# 17_MIPI_CSI_RX.net
KiCad netlist of a schematic drawn in Altium Designer
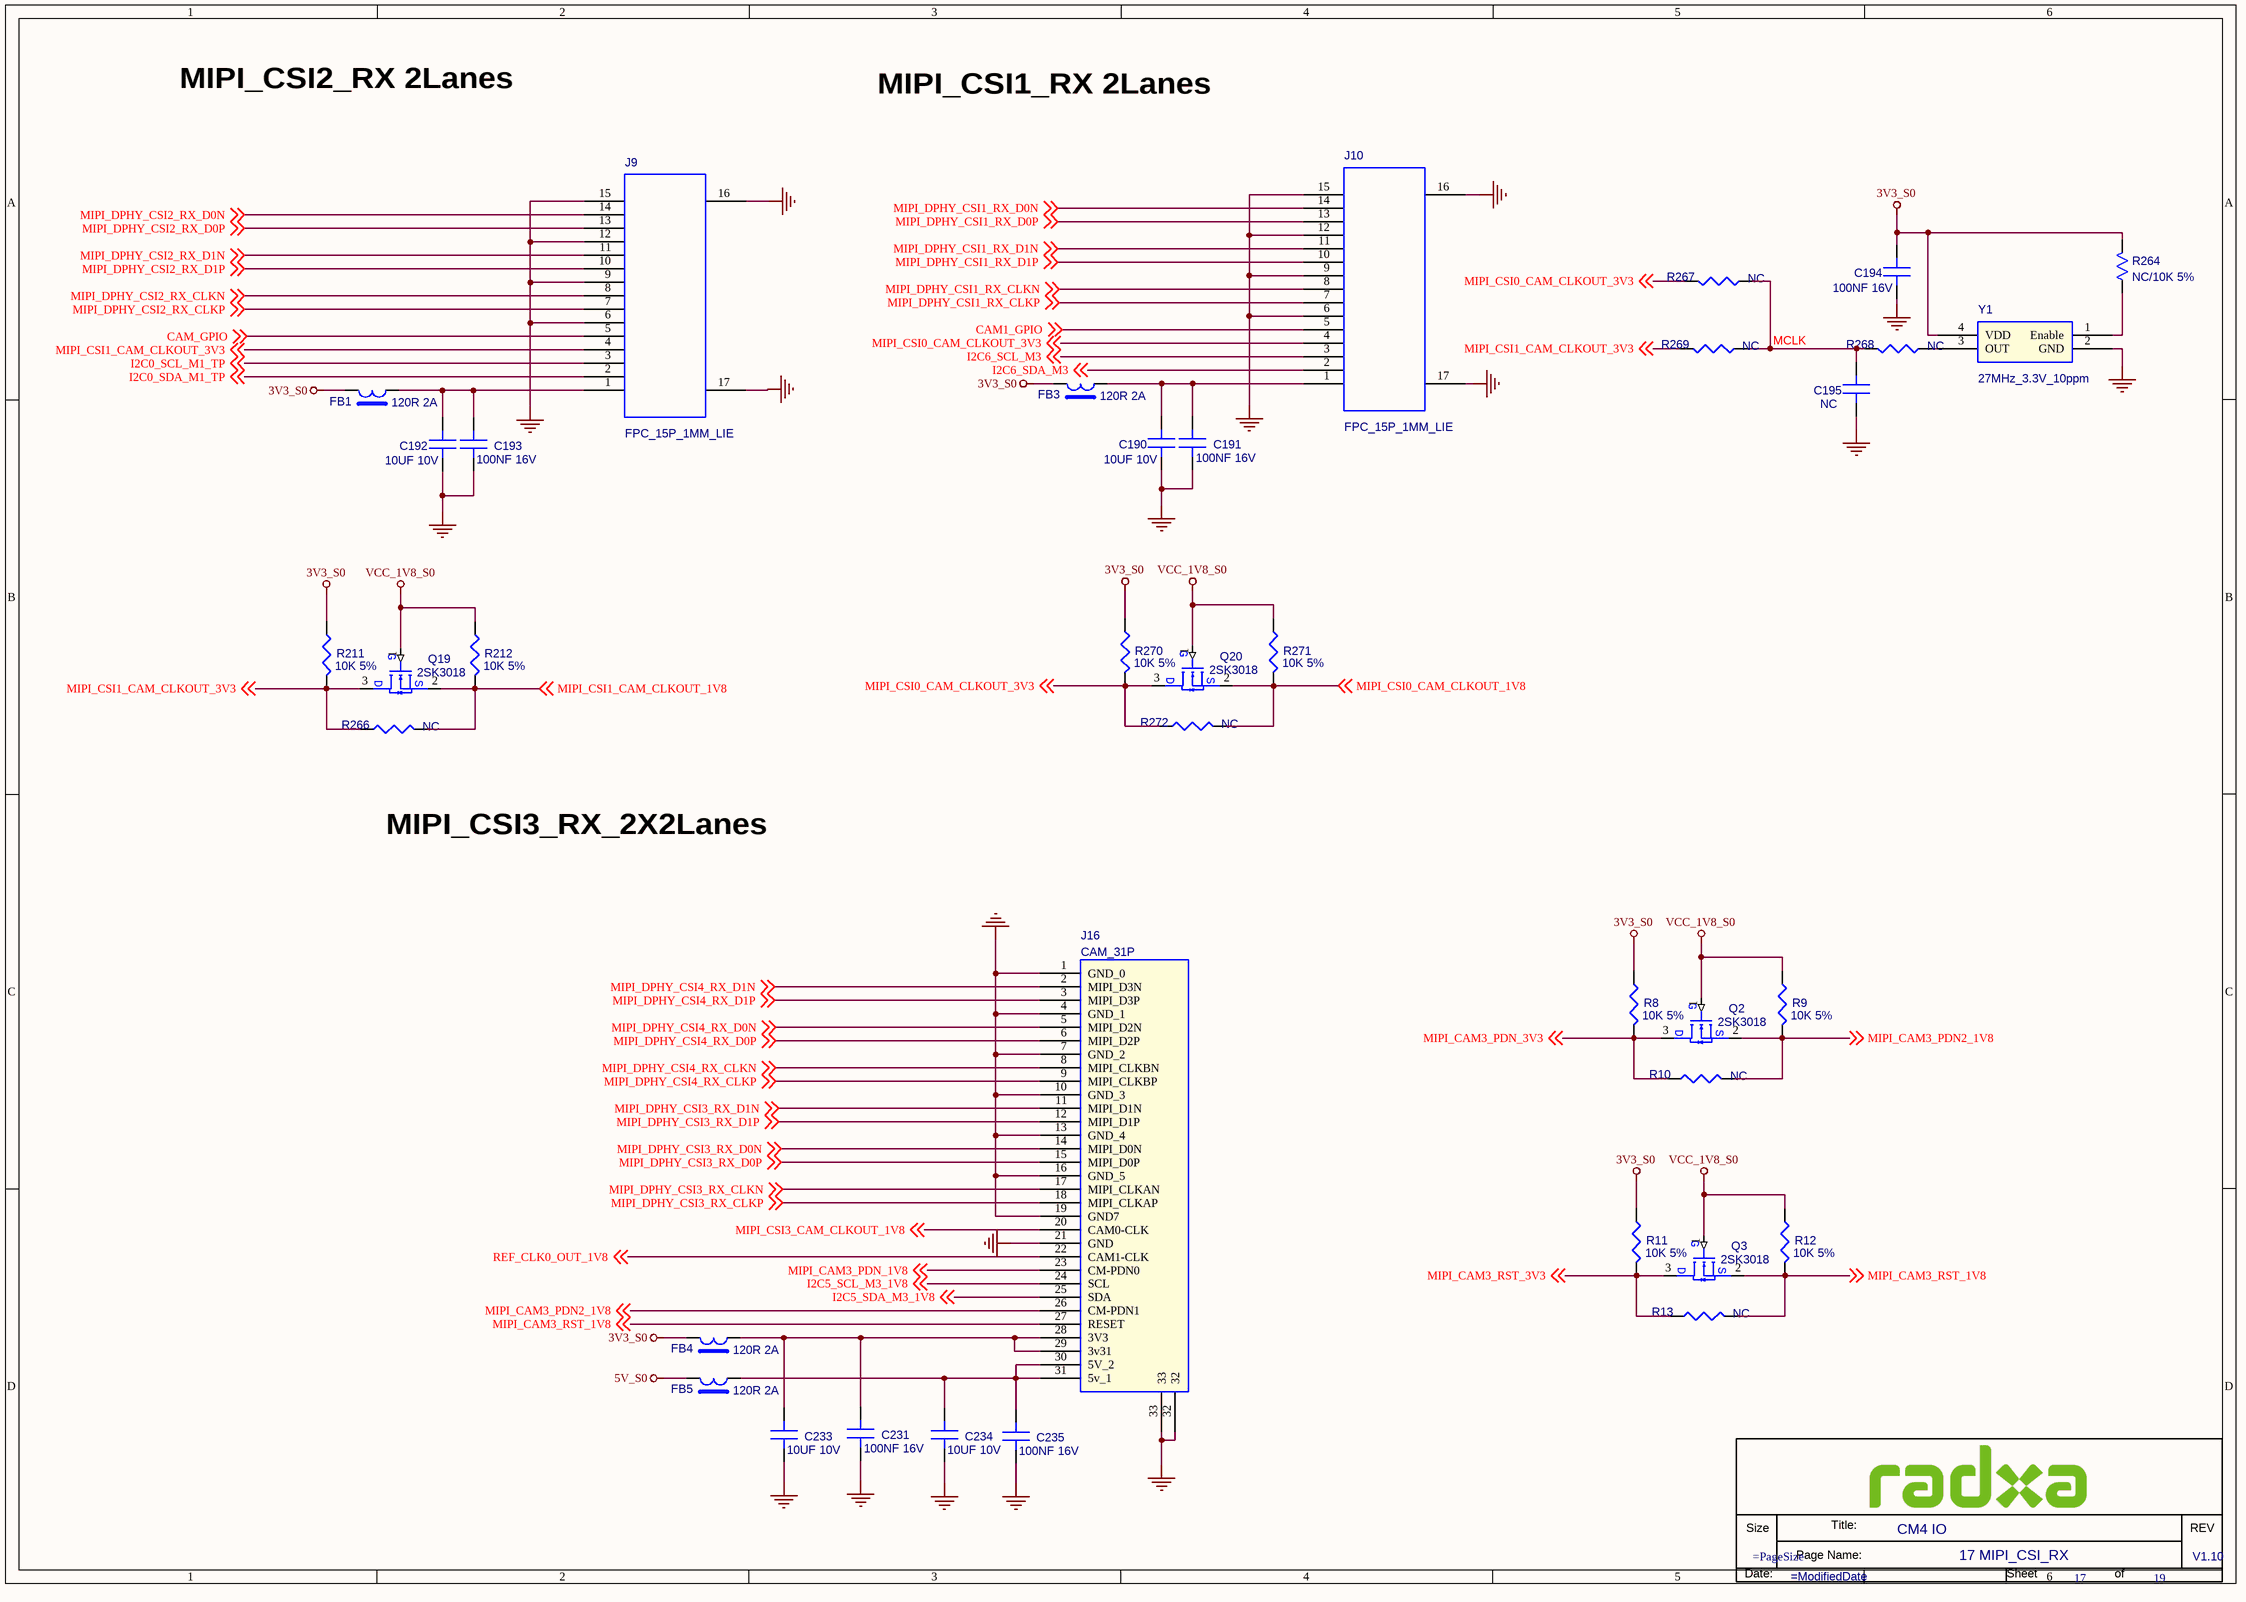
[diagram p0: 17 MIPI_CSI_RX.SchDoc]

(export (version "E")
  (design (tool "Eeschema 10.0.6"))
  (components
    (comp (ref "C190")
      (value "10UF 10V")
      (footprint "C0402")
      (description "SMD  0402  10UF  10V  X5R  ±20%  ROHS")
      (fields (field (name "PART NUMBER") "A1C01.00025"))
      (libsource (lib "*") (part "C"))
    )
    (comp (ref "C191")
      (value "100NF 16V")
      (footprint "C0201")
      (description "SMD  0201  100NF  16V  X5R  ±20%  ROHS")
      (fields (field (name "PART NUMBER") "A1C01.00099"))
      (libsource (lib "*") (part "C"))
    )
    (comp (ref "C192")
      (value "10UF 10V")
      (footprint "C0402")
      (description "SMD  0402  10UF  10V  X5R  ±20%  ROHS")
      (fields (field (name "PART NUMBER") "A1C01.00025"))
      (libsource (lib "*") (part "C"))
    )
    (comp (ref "C193")
      (value "100NF 16V")
      (footprint "C0201")
      (description "SMD  0201  100NF  16V  X5R  ±20%  ROHS")
      (fields (field (name "PART NUMBER") "A1C01.00099"))
      (libsource (lib "*") (part "C"))
    )
    (comp (ref "C194")
      (value "100NF 16V")
      (footprint "C0201")
      (description "SMD  0201  100NF  16V  X5R  ±20%  ROHS")
      (fields (field (name "PART NUMBER") "A1C01.00099") (field (name "APPROVED") "已承认"))
      (libsource (lib "*") (part "C_Dup1"))
    )
    (comp (ref "C195")
      (value "NC")
      (footprint "C0201")
      (description "SMD  0201  10PF  50V  NPO  ±5%  ROHS")
      (fields (field (name "PART NUMBER") "A1C01.00141") (field (name "APPROVED") "已承认"))
      (libsource (lib "*") (part "C_Dup1"))
    )
    (comp (ref "C231")
      (value "100NF 16V")
      (footprint "C0201")
      (description "SMD  0201  100NF  16V  X5R  ±20%  ROHS")
      (fields (field (name "PART NUMBER") "A1C01.00099"))
      (libsource (lib "*") (part "C"))
    )
    (comp (ref "C233")
      (value "10UF 10V")
      (footprint "C0402")
      (description "SMD  0402  10UF  10V  X5R  ±20%  ROHS")
      (fields (field (name "PART NUMBER") "A1C01.00025"))
      (libsource (lib "*") (part "C"))
    )
    (comp (ref "C234")
      (value "10UF 10V")
      (footprint "C0402")
      (description "SMD  0402  10UF  10V  X5R  ±20%  ROHS")
      (fields (field (name "PART NUMBER") "A1C01.00025"))
      (libsource (lib "*") (part "C"))
    )
    (comp (ref "C235")
      (value "100NF 16V")
      (footprint "C0201")
      (description "SMD  0201  100NF  16V  X5R  ±20%  ROHS")
      (fields (field (name "PART NUMBER") "A1C01.00099"))
      (libsource (lib "*") (part "C"))
    )
    (comp (ref "FB1")
      (value "120R 2A")
      (footprint "FB0402")
      (description "SMD  0402  FB120R  2A  ±25%  ROHS")
      (fields (field (name "PART NUMBER") "A1L09.00004"))
      (libsource (lib "*") (part "BEAD"))
    )
    (comp (ref "FB3")
      (value "120R 2A")
      (footprint "FB0402")
      (description "SMD  0402  FB120R  2A  ±25%  ROHS")
      (fields (field (name "PART NUMBER") "A1L09.00004"))
      (libsource (lib "*") (part "BEAD"))
    )
    (comp (ref "FB4")
      (value "120R 2A")
      (footprint "FB0402")
      (description "SMD  0402  FB120R  2A  ±25%  ROHS")
      (fields (field (name "PART NUMBER") "A1L09.00004"))
      (libsource (lib "*") (part "BEAD"))
    )
    (comp (ref "FB5")
      (value "120R 2A")
      (footprint "FB0402")
      (description "SMD  0402  FB120R  2A  ±25%  ROHS")
      (fields (field (name "PART NUMBER") "A1L09.00004"))
      (libsource (lib "*") (part "BEAD"))
    )
    (comp (ref "J9")
      (value "FPC_15P_1MM_LIE")
      (footprint "FPC_15_1D0_LIE")
      (description "SMD  翻盖式下接触  卧式  15PIN  180度  1.0mm脚距  H2.0  FPC-1.0FX-15PWCR-H20  XUNPU(讯普)  ROHS")
      (fields (field (name "PART NUMBER") "A1J06.00025"))
      (libsource (lib "*") (part "FPC_15P_LIE"))
    )
    (comp (ref "J10")
      (value "FPC_15P_1MM_LIE")
      (footprint "FPC_15_1D0_LIE")
      (description "SMD  翻盖式下接触  卧式  15PIN  180度  1.0mm脚距  H2.0  FPC-1.0FX-15PWCR-H20  XUNPU(讯普)  ROHS")
      (fields (field (name "PART NUMBER") "A1J06.00025"))
      (libsource (lib "*") (part "FPC_15P_LIE"))
    )
    (comp (ref "J16")
      (value "CAM_31P")
      (footprint "FPC_31P_0d3_LIE")
      (description "SMD  上下接触  卧式  31PIN  0.3mm脚距  后翻盖H1.0  FH35C-31S-0.3SHW(50)  镀金  广濑  ROHS")
      (fields (field (name "PART NUMBER") "A1J06.00002"))
      (libsource (lib "*") (part "CAM_31P"))
    )
    (comp (ref "Q2")
      (value "2SK3018")
      (footprint "SOT_323")
      (description "SMD  编带  SOT-323  2SK3018  N沟道  长晶  ROHS")
      (fields (field (name "PART NUMBER") "A1D01.00007"))
      (libsource (lib "*") (part "MOSFET_NPN"))
    )
    (comp (ref "Q3")
      (value "2SK3018")
      (footprint "SOT_323")
      (description "SMD  编带  SOT-323  2SK3018  N沟道  长晶  ROHS")
      (fields (field (name "PART NUMBER") "A1D01.00007"))
      (libsource (lib "*") (part "MOSFET_NPN"))
    )
    (comp (ref "Q19")
      (value "2SK3018")
      (footprint "SOT_323")
      (description "SMD  编带  SOT-323  2SK3018  N沟道  长晶  ROHS")
      (fields (field (name "PART NUMBER") "A1D01.00007"))
      (libsource (lib "*") (part "MOSFET_NPN"))
    )
    (comp (ref "Q20")
      (value "2SK3018")
      (footprint "SOT_323")
      (description "SMD  编带  SOT-323  2SK3018  N沟道  长晶  ROHS")
      (fields (field (name "PART NUMBER") "A1D01.00007"))
      (libsource (lib "*") (part "MOSFET_NPN"))
    )
    (comp (ref "R8")
      (value "10K 5%")
      (footprint "R0402")
      (description "SMD  0201  10K  1/20W  ±5%  ROHS")
      (fields (field (name "PART NUMBER") "A1R01.00012"))
      (libsource (lib "*") (part "R"))
    )
    (comp (ref "R9")
      (value "10K 5%")
      (footprint "R0402")
      (description "SMD  0201  10K  1/20W  ±5%  ROHS")
      (fields (field (name "PART NUMBER") "A1R01.00012"))
      (libsource (lib "*") (part "R"))
    )
    (comp (ref "R10")
      (value "NC")
      (footprint "R0402")
      (description "SMD  0201  0R  1/20W  ±5%  ROHS")
      (fields (field (name "PART NUMBER") "A1R01.00027"))
      (libsource (lib "*") (part "R"))
    )
    (comp (ref "R11")
      (value "10K 5%")
      (footprint "R0402")
      (description "SMD  0201  10K  1/20W  ±5%  ROHS")
      (fields (field (name "PART NUMBER") "A1R01.00012"))
      (libsource (lib "*") (part "R"))
    )
    (comp (ref "R12")
      (value "10K 5%")
      (footprint "R0402")
      (description "SMD  0201  10K  1/20W  ±5%  ROHS")
      (fields (field (name "PART NUMBER") "A1R01.00012"))
      (libsource (lib "*") (part "R"))
    )
    (comp (ref "R13")
      (value "NC")
      (footprint "R0402")
      (description "SMD  0201  0R  1/20W  ±5%  ROHS")
      (fields (field (name "PART NUMBER") "A1R01.00027"))
      (libsource (lib "*") (part "R"))
    )
    (comp (ref "R211")
      (value "10K 5%")
      (footprint "R0402")
      (description "SMD  0201  10K  1/20W  ±5%  ROHS")
      (fields (field (name "PART NUMBER") "A1R01.00012"))
      (libsource (lib "*") (part "R"))
    )
    (comp (ref "R212")
      (value "10K 5%")
      (footprint "R0402")
      (description "SMD  0201  10K  1/20W  ±5%  ROHS")
      (fields (field (name "PART NUMBER") "A1R01.00012"))
      (libsource (lib "*") (part "R"))
    )
    (comp (ref "R264")
      (value "NC/10K 5%")
      (footprint "R0201")
      (description "SMD  0201  10K  1/20W  ±5%  ROHS")
      (fields (field (name "PART NUMBER") "A1R01.00012") (field (name "APPROVED") "已承认"))
      (libsource (lib "*") (part "R_Dup1"))
    )
    (comp (ref "R266")
      (value "NC")
      (footprint "R0402")
      (description "SMD  0201  0R  1/20W  ±5%  ROHS")
      (fields (field (name "PART NUMBER") "A1R01.00027"))
      (libsource (lib "*") (part "R"))
    )
    (comp (ref "R267")
      (value "NC")
      (footprint "R0402")
      (description "SMD  0201  0R  1/20W  ±5%  ROHS")
      (fields (field (name "PART NUMBER") "A1R01.00027"))
      (libsource (lib "*") (part "R"))
    )
    (comp (ref "R268")
      (value "NC")
      (footprint "R0402")
      (description "SMD  0201  0R  1/20W  ±5%  ROHS")
      (fields (field (name "PART NUMBER") "A1R01.00027"))
      (libsource (lib "*") (part "R"))
    )
    (comp (ref "R269")
      (value "NC")
      (footprint "R0402")
      (description "SMD  0201  0R  1/20W  ±5%  ROHS")
      (fields (field (name "PART NUMBER") "A1R01.00027"))
      (libsource (lib "*") (part "R"))
    )
    (comp (ref "R270")
      (value "10K 5%")
      (footprint "R0402")
      (description "SMD  0201  10K  1/20W  ±5%  ROHS")
      (fields (field (name "PART NUMBER") "A1R01.00012"))
      (libsource (lib "*") (part "R"))
    )
    (comp (ref "R271")
      (value "10K 5%")
      (footprint "R0402")
      (description "SMD  0201  10K  1/20W  ±5%  ROHS")
      (fields (field (name "PART NUMBER") "A1R01.00012"))
      (libsource (lib "*") (part "R"))
    )
    (comp (ref "R272")
      (value "NC")
      (footprint "R0402")
      (description "SMD  0201  0R  1/20W  ±5%  ROHS")
      (fields (field (name "PART NUMBER") "A1R01.00027"))
      (libsource (lib "*") (part "R"))
    )
    (comp (ref "Y1")
      (value "27MHz_3.3V_10ppm")
      (footprint "Y-4-5_08-TXC-7W5")
      (description "SMD  有源  3225  27MHz  3.3V  ±10ppm  晶灏  3N27.000E33YCG  ROHS")
      (fields (field (name "PART NUMBER") "A1Y01.00074"))
      (libsource (lib "*") (part "OSC_4P_V"))
    )
  )
  (nets
    (net (code "1") (name "/MCLK") (class "Default")
      (node (ref "C195") (pin "1") (pinfunction "1_1") (pintype "passive"))
      (node (ref "R267") (pin "1") (pinfunction "1_1") (pintype "passive"))
      (node (ref "R268") (pin "1") (pinfunction "1_1") (pintype "passive"))
      (node (ref "R269") (pin "1") (pinfunction "1_1") (pintype "passive"))
    )
    (net (code "2") (name "3V3_S0") (class "Default")
      (node (ref "C194") (pin "1") (pinfunction "1_1") (pintype "passive"))
      (node (ref "FB1") (pin "2") (pinfunction "2_2") (pintype "passive"))
      (node (ref "FB3") (pin "2") (pinfunction "2_2") (pintype "passive"))
      (node (ref "FB4") (pin "2") (pinfunction "2_2") (pintype "passive"))
      (node (ref "R11") (pin "2") (pinfunction "2_2") (pintype "passive"))
      (node (ref "R211") (pin "2") (pinfunction "2_2") (pintype "passive"))
      (node (ref "R264") (pin "2") (pinfunction "2_2") (pintype "passive"))
      (node (ref "R270") (pin "2") (pinfunction "2_2") (pintype "passive"))
      (node (ref "R8") (pin "2") (pinfunction "2_2") (pintype "passive"))
      (node (ref "Y1") (pin "4") (pinfunction "VDD_4") (pintype "passive"))
    )
    (net (code "3") (name "5V_S0") (class "Default")
      (node (ref "FB5") (pin "2") (pinfunction "2_2") (pintype "passive"))
    )
    (net (code "4") (name "CAM1_GPIO") (class "Default")
      (node (ref "J10") (pin "5") (pinfunction "5_5") (pintype "passive"))
    )
    (net (code "5") (name "CAM_GPIO") (class "Default")
      (node (ref "J9") (pin "5") (pinfunction "5_5") (pintype "passive"))
    )
    (net (code "6") (name "GND") (class "Default")
      (node (ref "C190") (pin "2") (pinfunction "B_2") (pintype "passive"))
      (node (ref "C191") (pin "2") (pinfunction "B_2") (pintype "passive"))
      (node (ref "C192") (pin "2") (pinfunction "B_2") (pintype "passive"))
      (node (ref "C193") (pin "2") (pinfunction "B_2") (pintype "passive"))
      (node (ref "C194") (pin "2") (pinfunction "2_2") (pintype "passive"))
      (node (ref "C195") (pin "2") (pinfunction "2_2") (pintype "passive"))
      (node (ref "C231") (pin "2") (pinfunction "B_2") (pintype "passive"))
      (node (ref "C233") (pin "2") (pinfunction "B_2") (pintype "passive"))
      (node (ref "C234") (pin "2") (pinfunction "B_2") (pintype "passive"))
      (node (ref "C235") (pin "2") (pinfunction "B_2") (pintype "passive"))
      (node (ref "J10") (pin "12") (pinfunction "12_12") (pintype "passive"))
      (node (ref "J10") (pin "15") (pinfunction "15_15") (pintype "passive"))
      (node (ref "J10") (pin "16") (pinfunction "16_16") (pintype "passive"))
      (node (ref "J10") (pin "17") (pinfunction "17_17") (pintype "passive"))
      (node (ref "J10") (pin "6") (pinfunction "6_6") (pintype "passive"))
      (node (ref "J10") (pin "9") (pinfunction "9_9") (pintype "passive"))
      (node (ref "J16") (pin "1") (pinfunction "GND_0_1") (pintype "passive"))
      (node (ref "J16") (pin "10") (pinfunction "GND_3_10") (pintype "passive"))
      (node (ref "J16") (pin "13") (pinfunction "GND_4_13") (pintype "passive"))
      (node (ref "J16") (pin "16") (pinfunction "GND_5_16") (pintype "passive"))
      (node (ref "J16") (pin "19") (pinfunction "GND7_19") (pintype "passive"))
      (node (ref "J16") (pin "21") (pinfunction "GND_21") (pintype "passive"))
      (node (ref "J16") (pin "32") (pinfunction "32_32") (pintype "passive"))
      (node (ref "J16") (pin "33") (pinfunction "33_33") (pintype "passive"))
      (node (ref "J16") (pin "4") (pinfunction "GND_1_4") (pintype "passive"))
      (node (ref "J16") (pin "7") (pinfunction "GND_2_7") (pintype "passive"))
      (node (ref "J9") (pin "12") (pinfunction "12_12") (pintype "passive"))
      (node (ref "J9") (pin "15") (pinfunction "15_15") (pintype "passive"))
      (node (ref "J9") (pin "16") (pinfunction "16_16") (pintype "passive"))
      (node (ref "J9") (pin "17") (pinfunction "17_17") (pintype "passive"))
      (node (ref "J9") (pin "6") (pinfunction "6_6") (pintype "passive"))
      (node (ref "J9") (pin "9") (pinfunction "9_9") (pintype "passive"))
      (node (ref "Y1") (pin "2") (pinfunction "GND_2") (pintype "passive"))
    )
    (net (code "7") (name "I2C0_SCL_M1_TP") (class "Default")
      (node (ref "J9") (pin "3") (pinfunction "3_3") (pintype "passive"))
    )
    (net (code "8") (name "I2C0_SDA_M1_TP") (class "Default")
      (node (ref "J9") (pin "2") (pinfunction "2_2") (pintype "passive"))
    )
    (net (code "9") (name "I2C5_SCL_M3_1V8") (class "Default")
      (node (ref "J16") (pin "24") (pinfunction "SCL_24") (pintype "passive"))
    )
    (net (code "10") (name "I2C5_SDA_M3_1V8") (class "Default")
      (node (ref "J16") (pin "25") (pinfunction "SDA_25") (pintype "passive"))
    )
    (net (code "11") (name "I2C6_SCL_M3") (class "Default")
      (node (ref "J10") (pin "3") (pinfunction "3_3") (pintype "passive"))
    )
    (net (code "12") (name "I2C6_SDA_M3") (class "Default")
      (node (ref "J10") (pin "2") (pinfunction "2_2") (pintype "passive"))
    )
    (net (code "13") (name "MIPI_CAM3_PDN2_1V8") (class "Default")
      (node (ref "J16") (pin "26") (pinfunction "CM-PDN1_26") (pintype "passive"))
      (node (ref "Q2") (pin "2") (pinfunction "S_2") (pintype "passive"))
      (node (ref "R10") (pin "1") (pinfunction "1_1") (pintype "passive"))
      (node (ref "R9") (pin "1") (pinfunction "1_1") (pintype "passive"))
    )
    (net (code "14") (name "MIPI_CAM3_PDN_1V8") (class "Default")
      (node (ref "J16") (pin "23") (pinfunction "CM-PDN0_23") (pintype "passive"))
    )
    (net (code "15") (name "MIPI_CAM3_PDN_3V3") (class "Default")
      (node (ref "Q2") (pin "3") (pinfunction "D_3") (pintype "passive"))
      (node (ref "R10") (pin "2") (pinfunction "2_2") (pintype "passive"))
      (node (ref "R8") (pin "1") (pinfunction "1_1") (pintype "passive"))
    )
    (net (code "16") (name "MIPI_CAM3_RST_1V8") (class "Default")
      (node (ref "J16") (pin "27") (pinfunction "RESET_27") (pintype "passive"))
      (node (ref "Q3") (pin "2") (pinfunction "S_2") (pintype "passive"))
      (node (ref "R12") (pin "1") (pinfunction "1_1") (pintype "passive"))
      (node (ref "R13") (pin "1") (pinfunction "1_1") (pintype "passive"))
    )
    (net (code "17") (name "MIPI_CAM3_RST_3V3") (class "Default")
      (node (ref "Q3") (pin "3") (pinfunction "D_3") (pintype "passive"))
      (node (ref "R11") (pin "1") (pinfunction "1_1") (pintype "passive"))
      (node (ref "R13") (pin "2") (pinfunction "2_2") (pintype "passive"))
    )
    (net (code "18") (name "MIPI_CSI0_CAM_CLKOUT_1V8") (class "Default")
      (node (ref "Q20") (pin "2") (pinfunction "S_2") (pintype "passive"))
      (node (ref "R271") (pin "1") (pinfunction "1_1") (pintype "passive"))
      (node (ref "R272") (pin "1") (pinfunction "1_1") (pintype "passive"))
    )
    (net (code "19") (name "MIPI_CSI0_CAM_CLKOUT_3V3") (class "Default")
      (node (ref "J10") (pin "4") (pinfunction "4_4") (pintype "passive"))
      (node (ref "Q20") (pin "3") (pinfunction "D_3") (pintype "passive"))
      (node (ref "R267") (pin "2") (pinfunction "2_2") (pintype "passive"))
      (node (ref "R270") (pin "1") (pinfunction "1_1") (pintype "passive"))
      (node (ref "R272") (pin "2") (pinfunction "2_2") (pintype "passive"))
    )
    (net (code "20") (name "MIPI_CSI1_CAM_CLKOUT_1V8") (class "Default")
      (node (ref "Q19") (pin "2") (pinfunction "S_2") (pintype "passive"))
      (node (ref "R212") (pin "1") (pinfunction "1_1") (pintype "passive"))
      (node (ref "R266") (pin "1") (pinfunction "1_1") (pintype "passive"))
    )
    (net (code "21") (name "MIPI_CSI1_CAM_CLKOUT_3V3") (class "Default")
      (node (ref "J9") (pin "4") (pinfunction "4_4") (pintype "passive"))
      (node (ref "Q19") (pin "3") (pinfunction "D_3") (pintype "passive"))
      (node (ref "R211") (pin "1") (pinfunction "1_1") (pintype "passive"))
      (node (ref "R266") (pin "2") (pinfunction "2_2") (pintype "passive"))
      (node (ref "R269") (pin "2") (pinfunction "2_2") (pintype "passive"))
    )
    (net (code "22") (name "MIPI_CSI3_CAM_CLKOUT_1V8") (class "Default")
      (node (ref "J16") (pin "20") (pinfunction "CAM0-CLK_20") (pintype "passive"))
    )
    (net (code "23") (name "MIPI_DPHY_CSI1_RX_CLKN") (class "Default")
      (node (ref "J10") (pin "8") (pinfunction "8_8") (pintype "passive"))
    )
    (net (code "24") (name "MIPI_DPHY_CSI1_RX_CLKP") (class "Default")
      (node (ref "J10") (pin "7") (pinfunction "7_7") (pintype "passive"))
    )
    (net (code "25") (name "MIPI_DPHY_CSI1_RX_D0N") (class "Default")
      (node (ref "J10") (pin "14") (pinfunction "14_14") (pintype "passive"))
    )
    (net (code "26") (name "MIPI_DPHY_CSI1_RX_D0P") (class "Default")
      (node (ref "J10") (pin "13") (pinfunction "13_13") (pintype "passive"))
    )
    (net (code "27") (name "MIPI_DPHY_CSI1_RX_D1N") (class "Default")
      (node (ref "J10") (pin "11") (pinfunction "11_11") (pintype "passive"))
    )
    (net (code "28") (name "MIPI_DPHY_CSI1_RX_D1P") (class "Default")
      (node (ref "J10") (pin "10") (pinfunction "10_10") (pintype "passive"))
    )
    (net (code "29") (name "MIPI_DPHY_CSI2_RX_CLKN") (class "Default")
      (node (ref "J9") (pin "8") (pinfunction "8_8") (pintype "passive"))
    )
    (net (code "30") (name "MIPI_DPHY_CSI2_RX_CLKP") (class "Default")
      (node (ref "J9") (pin "7") (pinfunction "7_7") (pintype "passive"))
    )
    (net (code "31") (name "MIPI_DPHY_CSI2_RX_D0N") (class "Default")
      (node (ref "J9") (pin "14") (pinfunction "14_14") (pintype "passive"))
    )
    (net (code "32") (name "MIPI_DPHY_CSI2_RX_D0P") (class "Default")
      (node (ref "J9") (pin "13") (pinfunction "13_13") (pintype "passive"))
    )
    (net (code "33") (name "MIPI_DPHY_CSI2_RX_D1N") (class "Default")
      (node (ref "J9") (pin "11") (pinfunction "11_11") (pintype "passive"))
    )
    (net (code "34") (name "MIPI_DPHY_CSI2_RX_D1P") (class "Default")
      (node (ref "J9") (pin "10") (pinfunction "10_10") (pintype "passive"))
    )
    (net (code "35") (name "MIPI_DPHY_CSI3_RX_CLKN") (class "Default")
      (node (ref "J16") (pin "17") (pinfunction "MIPI_CLKAN_17") (pintype "passive"))
    )
    (net (code "36") (name "MIPI_DPHY_CSI3_RX_CLKP") (class "Default")
      (node (ref "J16") (pin "18") (pinfunction "MIPI_CLKAP_18") (pintype "passive"))
    )
    (net (code "37") (name "MIPI_DPHY_CSI3_RX_D0N") (class "Default")
      (node (ref "J16") (pin "14") (pinfunction "MIPI_D0N_14") (pintype "passive"))
    )
    (net (code "38") (name "MIPI_DPHY_CSI3_RX_D0P") (class "Default")
      (node (ref "J16") (pin "15") (pinfunction "MIPI_D0P_15") (pintype "passive"))
    )
    (net (code "39") (name "MIPI_DPHY_CSI3_RX_D1N") (class "Default")
      (node (ref "J16") (pin "11") (pinfunction "MIPI_D1N_11") (pintype "passive"))
    )
    (net (code "40") (name "MIPI_DPHY_CSI3_RX_D1P") (class "Default")
      (node (ref "J16") (pin "12") (pinfunction "MIPI_D1P_12") (pintype "passive"))
    )
    (net (code "41") (name "MIPI_DPHY_CSI4_RX_CLKN") (class "Default")
      (node (ref "J16") (pin "8") (pinfunction "MIPI_CLKBN_8") (pintype "passive"))
    )
    (net (code "42") (name "MIPI_DPHY_CSI4_RX_CLKP") (class "Default")
      (node (ref "J16") (pin "9") (pinfunction "MIPI_CLKBP_9") (pintype "passive"))
    )
    (net (code "43") (name "MIPI_DPHY_CSI4_RX_D0N") (class "Default")
      (node (ref "J16") (pin "5") (pinfunction "MIPI_D2N_5") (pintype "passive"))
    )
    (net (code "44") (name "MIPI_DPHY_CSI4_RX_D0P") (class "Default")
      (node (ref "J16") (pin "6") (pinfunction "MIPI_D2P_6") (pintype "passive"))
    )
    (net (code "45") (name "MIPI_DPHY_CSI4_RX_D1N") (class "Default")
      (node (ref "J16") (pin "2") (pinfunction "MIPI_D3N_2") (pintype "passive"))
    )
    (net (code "46") (name "MIPI_DPHY_CSI4_RX_D1P") (class "Default")
      (node (ref "J16") (pin "3") (pinfunction "MIPI_D3P_3") (pintype "passive"))
    )
    (net (code "47") (name "Net-(C190-A)") (class "Default")
      (node (ref "C190") (pin "1") (pinfunction "A_1") (pintype "passive"))
      (node (ref "C191") (pin "1") (pinfunction "A_1") (pintype "passive"))
      (node (ref "FB3") (pin "1") (pinfunction "1_1") (pintype "passive"))
      (node (ref "J10") (pin "1") (pinfunction "1_1") (pintype "passive"))
    )
    (net (code "48") (name "Net-(C192-A)") (class "Default")
      (node (ref "C192") (pin "1") (pinfunction "A_1") (pintype "passive"))
      (node (ref "C193") (pin "1") (pinfunction "A_1") (pintype "passive"))
      (node (ref "FB1") (pin "1") (pinfunction "1_1") (pintype "passive"))
      (node (ref "J9") (pin "1") (pinfunction "1_1") (pintype "passive"))
    )
    (net (code "49") (name "Net-(C231-A)") (class "Default")
      (node (ref "C231") (pin "1") (pinfunction "A_1") (pintype "passive"))
      (node (ref "C233") (pin "1") (pinfunction "A_1") (pintype "passive"))
      (node (ref "FB4") (pin "1") (pinfunction "1_1") (pintype "passive"))
      (node (ref "J16") (pin "28") (pinfunction "3V3_28") (pintype "passive"))
      (node (ref "J16") (pin "29") (pinfunction "3v31_29") (pintype "passive"))
    )
    (net (code "50") (name "Net-(C234-A)") (class "Default")
      (node (ref "C234") (pin "1") (pinfunction "A_1") (pintype "passive"))
      (node (ref "C235") (pin "1") (pinfunction "A_1") (pintype "passive"))
      (node (ref "FB5") (pin "1") (pinfunction "1_1") (pintype "passive"))
      (node (ref "J16") (pin "30") (pinfunction "5V_2_30") (pintype "passive"))
      (node (ref "J16") (pin "31") (pinfunction "5v_1_31") (pintype "passive"))
    )
    (net (code "51") (name "Net-(Y1-Enable)") (class "Default")
      (node (ref "R264") (pin "1") (pinfunction "1_1") (pintype "passive"))
      (node (ref "Y1") (pin "1") (pinfunction "Enable_1") (pintype "passive"))
    )
    (net (code "52") (name "Net-(Y1-OUT)") (class "Default")
      (node (ref "R268") (pin "2") (pinfunction "2_2") (pintype "passive"))
      (node (ref "Y1") (pin "3") (pinfunction "OUT_3") (pintype "passive"))
    )
    (net (code "53") (name "REF_CLK0_OUT_1V8") (class "Default")
      (node (ref "J16") (pin "22") (pinfunction "CAM1-CLK_22") (pintype "passive"))
    )
    (net (code "54") (name "VCC_1V8_S0") (class "Default")
      (node (ref "Q19") (pin "1") (pinfunction "G_1") (pintype "input"))
      (node (ref "Q2") (pin "1") (pinfunction "G_1") (pintype "input"))
      (node (ref "Q20") (pin "1") (pinfunction "G_1") (pintype "input"))
      (node (ref "Q3") (pin "1") (pinfunction "G_1") (pintype "input"))
      (node (ref "R12") (pin "2") (pinfunction "2_2") (pintype "passive"))
      (node (ref "R212") (pin "2") (pinfunction "2_2") (pintype "passive"))
      (node (ref "R271") (pin "2") (pinfunction "2_2") (pintype "passive"))
      (node (ref "R9") (pin "2") (pinfunction "2_2") (pintype "passive"))
    )
  )
)
